# IMU.net
KiCad netlist of a schematic drawn in Altium Designer
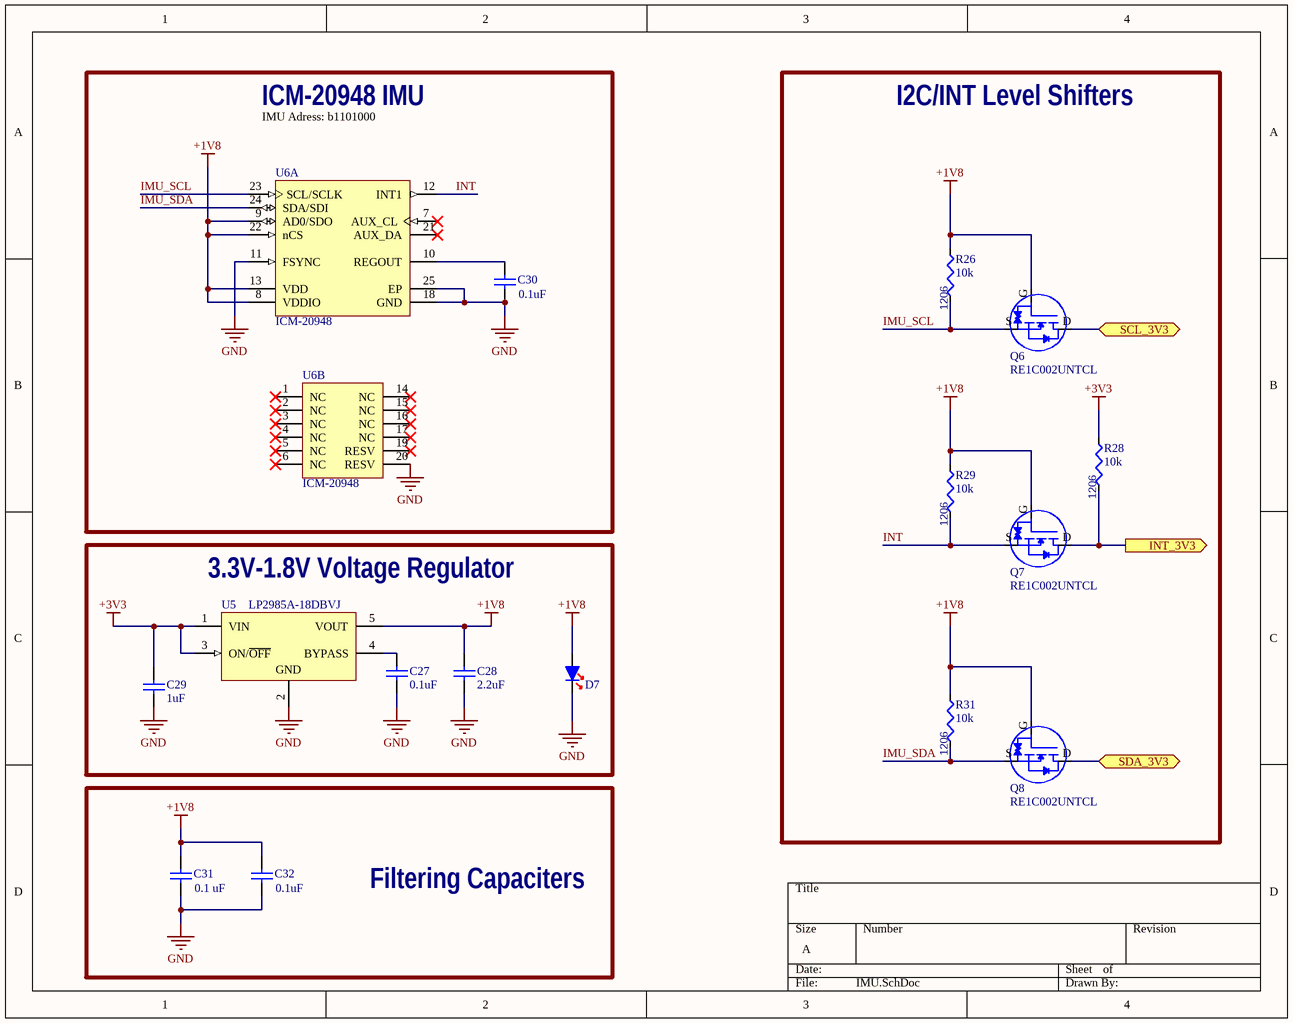
[diagram p0: IMU.SchDoc]

(export (version "E")
  (design (tool "Eeschema 10.0.6"))
  (components
    (comp (ref "C27")
      (value "0.1uF")
      (footprint "GMC10X7R104J10NT-Footprint-1")
      (description "0.1 µF ±5% 10V Ceramic Capacitor X7R 0603 (1608 Metric)")
      (libsource (lib "USCRPL") (part "GMC10X7R104J10NT-Symbol-1"))
    )
    (comp (ref "C28")
      (value "2.2uF")
      (footprint "C1206")
      (description "CAP CER 2.2UF 50V X7R 1206")
      (libsource (lib "") (part "Symbol_1"))
    )
    (comp (ref "C29")
      (value "1uF")
      (footprint "C1206")
      (description "CER 1UF 50V X7R 1206")
      (fields (field (name "REVIEWED BY") "Carter Allen") (field (name "MADE BY") "Brennan Swanton"))
      (libsource (lib "") (part "Symbol_1"))
    )
    (comp (ref "C30")
      (value "0.1uF")
      (footprint "GMC10X7R104J10NT-Footprint-1")
      (description "0.1 µF ±5% 10V Ceramic Capacitor X7R 0603 (1608 Metric)")
      (libsource (lib "USCRPL") (part "GMC10X7R104J10NT-Symbol-1"))
    )
    (comp (ref "C31")
      (value "0.1 uF")
      (footprint "GMC10X7R104J10NT-Footprint-1")
      (description "0.1 µF ±5% 10V Ceramic Capacitor X7R 0603 (1608 Metric)")
      (libsource (lib "USCRPL") (part "GMC10X7R104J10NT-Symbol-1"))
    )
    (comp (ref "C32")
      (value "0.1uF")
      (footprint "GMC10X7R104J10NT-Footprint-1")
      (description "0.1 µF ±5% 10V Ceramic Capacitor X7R 0603 (1608 Metric)")
      (libsource (lib "USCRPL") (part "GMC10X7R104J10NT-Symbol-1"))
    )
    (comp (ref "D7")
      (value "AA3528LSECKT/J3")
      (footprint "New footprint 1")
      (description "Red 625nm LED Indication - Discrete 1.8V 2-PLCC")
      (libsource (lib "USCRPL") (part "New symbol 1"))
    )
    (comp (ref "Q6")
      (value "RE1C002UNTCL")
      (footprint "DIO_RB558WMF_ROM")
      (description "No Description Available")
      (fields (field (name "COPYRIGHT") "Copyright (C) 2024 Ultra Librarian. All rights reserved."))
      (libsource (lib "RE1C002UNTCL") (part "RE1C002UNTCL"))
    )
    (comp (ref "Q7")
      (value "RE1C002UNTCL")
      (footprint "DIO_RB558WMF_ROM")
      (description "No Description Available")
      (fields (field (name "COPYRIGHT") "Copyright (C) 2024 Ultra Librarian. All rights reserved."))
      (libsource (lib "RE1C002UNTCL") (part "RE1C002UNTCL"))
    )
    (comp (ref "Q8")
      (value "RE1C002UNTCL")
      (footprint "DIO_RB558WMF_ROM")
      (description "No Description Available")
      (fields (field (name "COPYRIGHT") "Copyright (C) 2024 Ultra Librarian. All rights reserved."))
      (libsource (lib "RE1C002UNTCL") (part "RE1C002UNTCL"))
    )
    (comp (ref "R26")
      (value "10k")
      (footprint "R1206")
      (description "10K OHM 1% 1/4W 1206")
      (fields (field (name "MADE BY") "Brennan Swanton") (field (name "REVIEWED BY") "Carter Allen"))
      (libsource (lib "USCRPL") (part "Symbol"))
    )
    (comp (ref "R28")
      (value "10k")
      (footprint "R1206")
      (description "10K OHM 1% 1/4W 1206")
      (fields (field (name "MADE BY") "Brennan Swanton") (field (name "REVIEWED BY") "Carter Allen"))
      (libsource (lib "USCRPL") (part "Symbol"))
    )
    (comp (ref "R29")
      (value "10k")
      (footprint "R1206")
      (description "10K OHM 1% 1/4W 1206")
      (fields (field (name "MADE BY") "Brennan Swanton") (field (name "REVIEWED BY") "Carter Allen"))
      (libsource (lib "USCRPL") (part "Symbol"))
    )
    (comp (ref "R31")
      (value "10k")
      (footprint "R1206")
      (description "10K OHM 1% 1/4W 1206")
      (fields (field (name "MADE BY") "Brennan Swanton") (field (name "REVIEWED BY") "Carter Allen"))
      (libsource (lib "USCRPL") (part "Symbol"))
    )
    (comp (ref "U5")
      (value "LP2985A-18DBVJ")
      (footprint "DBV0005A_L")
      (fields (field (name "MANUFACTURER") "Texas Instruments"))
      (libsource (lib "Altium Content Vault") (part "TI-LP2985_A-10DBV5"))
    )
    (comp (ref "U6")
      (value "ICM-20948")
      (footprint "TDK-QFN-24_L")
      (fields (field (name "MANUFACTURER") "TDK"))
      (libsource (lib "Altium Content Vault") (part "TDK-ICM-20948-QFN-24"))
    )
  )
  (nets
    (net (code "1") (name "+1V8") (class "Default")
      (node (ref "C28") (pin "2") (pinfunction "2_2") (pintype "passive"))
      (node (ref "C31") (pin "2") (pinfunction "2_2") (pintype "passive"))
      (node (ref "C32") (pin "2") (pinfunction "2_2") (pintype "passive"))
      (node (ref "D7") (pin "2") (pinfunction "2_2") (pintype "passive"))
      (node (ref "Q6") (pin "G") (pinfunction "G_G") (pintype "passive"))
      (node (ref "Q7") (pin "G") (pinfunction "G_G") (pintype "passive"))
      (node (ref "Q8") (pin "G") (pinfunction "G_G") (pintype "passive"))
      (node (ref "R26") (pin "2") (pinfunction "2_2") (pintype "passive"))
      (node (ref "R29") (pin "2") (pinfunction "2_2") (pintype "passive"))
      (node (ref "R31") (pin "2") (pinfunction "2_2") (pintype "passive"))
      (node (ref "U5") (pin "5") (pinfunction "VOUT_5") (pintype "power_in"))
      (node (ref "U6") (pin "13") (pinfunction "VDD_13") (pintype "power_in"))
      (node (ref "U6") (pin "22") (pinfunction "nCS_22") (pintype "input"))
      (node (ref "U6") (pin "8") (pinfunction "VDDIO_8") (pintype "power_in"))
      (node (ref "U6") (pin "9") (pinfunction "AD0/SDO_9") (pintype "bidirectional"))
    )
    (net (code "2") (name "+3V3") (class "Default")
      (node (ref "C29") (pin "2") (pinfunction "2_2") (pintype "passive"))
      (node (ref "R28") (pin "2") (pinfunction "2_2") (pintype "passive"))
      (node (ref "U5") (pin "1") (pinfunction "VIN_1") (pintype "power_in"))
      (node (ref "U5") (pin "3") (pinfunction "ON/~{OFF}_3") (pintype "input"))
    )
    (net (code "3") (name "/IMU_SCL") (class "Default")
      (node (ref "Q6") (pin "S") (pinfunction "S_S") (pintype "passive"))
      (node (ref "R26") (pin "1") (pinfunction "1_1") (pintype "passive"))
      (node (ref "U6") (pin "23") (pinfunction "SCL/SCLK_23") (pintype "input"))
    )
    (net (code "4") (name "/IMU_SDA") (class "Default")
      (node (ref "Q8") (pin "S") (pinfunction "S_S") (pintype "passive"))
      (node (ref "R31") (pin "1") (pinfunction "1_1") (pintype "passive"))
      (node (ref "U6") (pin "24") (pinfunction "SDA/SDI_24") (pintype "bidirectional"))
    )
    (net (code "5") (name "/INT") (class "Default")
      (node (ref "Q7") (pin "S") (pinfunction "S_S") (pintype "passive"))
      (node (ref "R29") (pin "1") (pinfunction "1_1") (pintype "passive"))
      (node (ref "U6") (pin "12") (pinfunction "INT1_12") (pintype "output"))
    )
    (net (code "6") (name "/INT_3V3") (class "Default")
      (node (ref "Q7") (pin "D") (pinfunction "D_D") (pintype "passive"))
      (node (ref "R28") (pin "1") (pinfunction "1_1") (pintype "passive"))
    )
    (net (code "7") (name "/SCL_3V3") (class "Default")
      (node (ref "Q6") (pin "D") (pinfunction "D_D") (pintype "passive"))
    )
    (net (code "8") (name "/SDA_3V3") (class "Default")
      (node (ref "Q8") (pin "D") (pinfunction "D_D") (pintype "passive"))
    )
    (net (code "9") (name "GND") (class "Default")
      (node (ref "C27") (pin "1") (pinfunction "1_1") (pintype "passive"))
      (node (ref "C28") (pin "1") (pinfunction "1_1") (pintype "passive"))
      (node (ref "C29") (pin "1") (pinfunction "1_1") (pintype "passive"))
      (node (ref "C30") (pin "1") (pinfunction "1_1") (pintype "passive"))
      (node (ref "C31") (pin "1") (pinfunction "1_1") (pintype "passive"))
      (node (ref "C32") (pin "1") (pinfunction "1_1") (pintype "passive"))
      (node (ref "D7") (pin "1") (pinfunction "1_1") (pintype "passive"))
      (node (ref "U5") (pin "2") (pinfunction "GND_2") (pintype "power_in"))
      (node (ref "U6") (pin "11") (pinfunction "FSYNC_11") (pintype "input"))
      (node (ref "U6") (pin "18") (pinfunction "GND_18") (pintype "power_in"))
      (node (ref "U6") (pin "20") (pinfunction "RESV_20") (pintype "passive"))
      (node (ref "U6") (pin "25") (pinfunction "EP_25") (pintype "passive"))
    )
    (net (code "10") (name "Net-(U5-BYPASS)") (class "Default")
      (node (ref "C27") (pin "2") (pinfunction "2_2") (pintype "passive"))
      (node (ref "U5") (pin "4") (pinfunction "BYPASS_4") (pintype "passive"))
    )
    (net (code "11") (name "Net-(U6A-REGOUT)") (class "Default")
      (node (ref "C30") (pin "2") (pinfunction "2_2") (pintype "passive"))
      (node (ref "U6") (pin "10") (pinfunction "REGOUT_10") (pintype "passive"))
    )
    (net (code "12") (name "unconnected-(U6A-AUX_CL-Pad7)") (class "Default")
      (node (ref "U6") (pin "7") (pinfunction "AUX_CL_7") (pintype "input+no_connect"))
    )
    (net (code "13") (name "unconnected-(U6A-AUX_DA-Pad21)") (class "Default")
      (node (ref "U6") (pin "21") (pinfunction "AUX_DA_21") (pintype "passive+no_connect"))
    )
    (net (code "14") (name "unconnected-(U6B-NC-Pad1)") (class "Default")
      (node (ref "U6") (pin "1") (pinfunction "NC_1") (pintype "passive+no_connect"))
    )
    (net (code "15") (name "unconnected-(U6B-NC-Pad2)") (class "Default")
      (node (ref "U6") (pin "2") (pinfunction "NC_2") (pintype "passive+no_connect"))
    )
    (net (code "16") (name "unconnected-(U6B-NC-Pad3)") (class "Default")
      (node (ref "U6") (pin "3") (pinfunction "NC_3") (pintype "passive+no_connect"))
    )
    (net (code "17") (name "unconnected-(U6B-NC-Pad4)") (class "Default")
      (node (ref "U6") (pin "4") (pinfunction "NC_4") (pintype "passive+no_connect"))
    )
    (net (code "18") (name "unconnected-(U6B-NC-Pad5)") (class "Default")
      (node (ref "U6") (pin "5") (pinfunction "NC_5") (pintype "passive+no_connect"))
    )
    (net (code "19") (name "unconnected-(U6B-NC-Pad6)") (class "Default")
      (node (ref "U6") (pin "6") (pinfunction "NC_6") (pintype "passive+no_connect"))
    )
    (net (code "20") (name "unconnected-(U6B-NC-Pad14)") (class "Default")
      (node (ref "U6") (pin "14") (pinfunction "NC_14") (pintype "passive+no_connect"))
    )
    (net (code "21") (name "unconnected-(U6B-NC-Pad15)") (class "Default")
      (node (ref "U6") (pin "15") (pinfunction "NC_15") (pintype "passive+no_connect"))
    )
    (net (code "22") (name "unconnected-(U6B-NC-Pad16)") (class "Default")
      (node (ref "U6") (pin "16") (pinfunction "NC_16") (pintype "passive+no_connect"))
    )
    (net (code "23") (name "unconnected-(U6B-NC-Pad17)") (class "Default")
      (node (ref "U6") (pin "17") (pinfunction "NC_17") (pintype "passive+no_connect"))
    )
    (net (code "24") (name "unconnected-(U6B-RESV-Pad19)") (class "Default")
      (node (ref "U6") (pin "19") (pinfunction "RESV_19") (pintype "passive+no_connect"))
    )
  )
)
